# WisolWSSFM10R2-Breakout.net
KiCad netlist of a schematic drawn in EAGLE
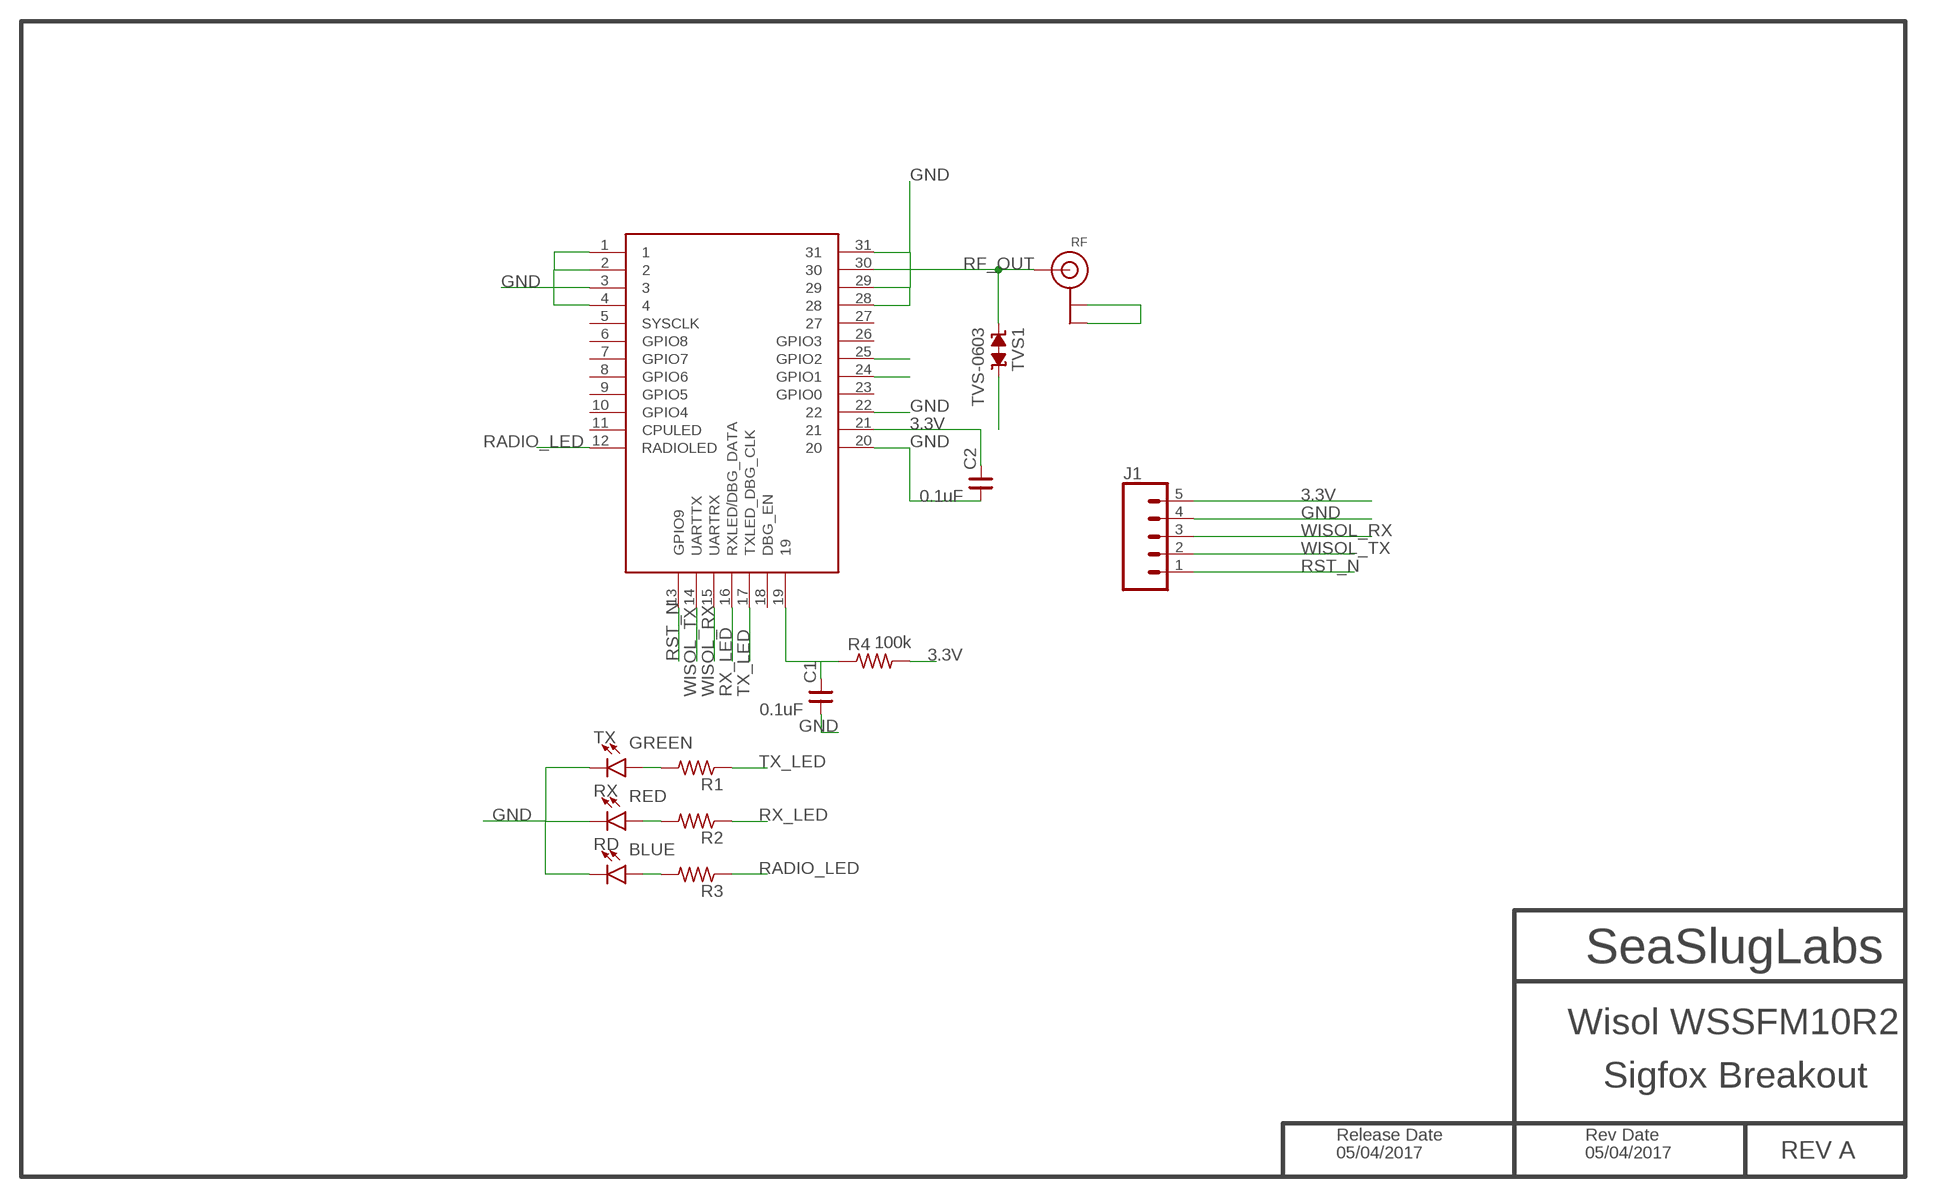
[diagram p0: schematic, sheet 1]

(export (version "E")
  (design (tool "Eeschema 10.0.6"))
  (components
    (comp (ref "C1")
      (value "0.1uF")
      (footprint "eagle-import:0402")
      (libsource (lib "eagle-import") (part "CNP-0402"))
    )
    (comp (ref "C2")
      (value "0.1uF")
      (footprint "eagle-import:0402")
      (libsource (lib "eagle-import") (part "CNP-0402"))
    )
    (comp (ref "J1")
      (value "CONN_05")
      (footprint "eagle-import:1X05")
      (libsource (lib "eagle-import") (part "CONN_05"))
    )
    (comp (ref "R1")
      (value "R-US_R0402")
      (footprint "eagle-import:R0402")
      (libsource (lib "eagle-import") (part "R-US_R0402"))
    )
    (comp (ref "R2")
      (value "R-US_R0402")
      (footprint "eagle-import:R0402")
      (libsource (lib "eagle-import") (part "R-US_R0402"))
    )
    (comp (ref "R3")
      (value "R-US_R0402")
      (footprint "eagle-import:R0402")
      (libsource (lib "eagle-import") (part "R-US_R0402"))
    )
    (comp (ref "R4")
      (value "100k")
      (footprint "eagle-import:R0402")
      (libsource (lib "eagle-import") (part "R-US_R0402"))
    )
    (comp (ref "RD")
      (value "BLUE")
      (footprint "eagle-import:LED-0603")
      (libsource (lib "eagle-import") (part "LED-BLUE0603"))
    )
    (comp (ref "RF")
      (value "ANTENNA_U.FL")
      (footprint "eagle-import:U.FL")
      (libsource (lib "eagle-import") (part "ANTENNA_U.FL"))
    )
    (comp (ref "RX")
      (value "RED")
      (footprint "eagle-import:LED-0603")
      (libsource (lib "eagle-import") (part "LED-RED0603"))
    )
    (comp (ref "TVS1")
      (value "TVS-0603")
      (footprint "eagle-import:TVS0603")
      (libsource (lib "eagle-import") (part "TVS-0603"))
    )
    (comp (ref "TX")
      (value "GREEN")
      (footprint "eagle-import:LED-0603")
      (libsource (lib "eagle-import") (part "LED-GREEN0603"))
    )
    (comp (ref "WSSFM10R2")
      (value "WSSFM10R2/R4WSSFM10R2R4")
      (footprint "eagle-import:WISOL")
      (libsource (lib "eagle-import") (part "WSSFM10R2/R4WSSFM10R2R4"))
    )
  )
  (nets
    (net (code "1") (name "/3.3V") (class "Default")
      (node (ref "C2") (pin "2") (pinfunction "2_2") (pintype "passive"))
      (node (ref "J1") (pin "5") (pinfunction "5_5") (pintype "passive"))
      (node (ref "R4") (pin "2") (pinfunction "2_2") (pintype "passive"))
      (node (ref "WSSFM10R2") (pin "21") (pinfunction "21_21") (pintype "bidirectional"))
    )
    (net (code "2") (name "/GND") (class "Default")
      (node (ref "C1") (pin "1") (pinfunction "1_1") (pintype "passive"))
      (node (ref "C2") (pin "1") (pinfunction "1_1") (pintype "passive"))
      (node (ref "J1") (pin "4") (pinfunction "4_4") (pintype "passive"))
      (node (ref "RD") (pin "C") (pinfunction "C_C") (pintype "passive"))
      (node (ref "RF") (pin "1") (pinfunction "GND_1") (pintype "passive"))
      (node (ref "RF") (pin "2") (pinfunction "GND_2") (pintype "passive"))
      (node (ref "RX") (pin "C") (pinfunction "C_C") (pintype "passive"))
      (node (ref "TVS1") (pin "2") (pinfunction "2_2") (pintype "passive"))
      (node (ref "TX") (pin "C") (pinfunction "C_C") (pintype "passive"))
      (node (ref "WSSFM10R2") (pin "1") (pinfunction "1_1") (pintype "bidirectional"))
      (node (ref "WSSFM10R2") (pin "2") (pinfunction "2_2") (pintype "bidirectional"))
      (node (ref "WSSFM10R2") (pin "20") (pinfunction "20_20") (pintype "bidirectional"))
      (node (ref "WSSFM10R2") (pin "22") (pinfunction "22_22") (pintype "bidirectional"))
      (node (ref "WSSFM10R2") (pin "28") (pinfunction "28_28") (pintype "bidirectional"))
      (node (ref "WSSFM10R2") (pin "29") (pinfunction "29_29") (pintype "bidirectional"))
      (node (ref "WSSFM10R2") (pin "3") (pinfunction "3_3") (pintype "bidirectional"))
      (node (ref "WSSFM10R2") (pin "31") (pinfunction "31_31") (pintype "bidirectional"))
      (node (ref "WSSFM10R2") (pin "4") (pinfunction "4_4") (pintype "bidirectional"))
    )
    (net (code "3") (name "/RADIO_LED") (class "Default")
      (node (ref "R3") (pin "1") (pinfunction "1_1") (pintype "passive"))
      (node (ref "WSSFM10R2") (pin "12") (pinfunction "RADIOLED_12") (pintype "bidirectional"))
    )
    (net (code "4") (name "/RF_OUT") (class "Default")
      (node (ref "RF") (pin "3") (pinfunction "SIGNAL_3") (pintype "passive"))
      (node (ref "TVS1") (pin "1") (pinfunction "1_1") (pintype "passive"))
      (node (ref "WSSFM10R2") (pin "30") (pinfunction "30_30") (pintype "bidirectional"))
    )
    (net (code "5") (name "/RST_N") (class "Default")
      (node (ref "J1") (pin "1") (pinfunction "1_1") (pintype "passive"))
      (node (ref "WSSFM10R2") (pin "13") (pinfunction "GPIO9_13") (pintype "bidirectional"))
    )
    (net (code "6") (name "/RX_LED") (class "Default")
      (node (ref "R2") (pin "1") (pinfunction "1_1") (pintype "passive"))
      (node (ref "WSSFM10R2") (pin "16") (pinfunction "RXLED/DBG_DATA_16") (pintype "bidirectional"))
    )
    (net (code "7") (name "/TX_LED") (class "Default")
      (node (ref "R1") (pin "1") (pinfunction "1_1") (pintype "passive"))
      (node (ref "WSSFM10R2") (pin "17") (pinfunction "TXLED_DBG_CLK_17") (pintype "bidirectional"))
    )
    (net (code "8") (name "/WISOL_RX") (class "Default")
      (node (ref "J1") (pin "3") (pinfunction "3_3") (pintype "passive"))
      (node (ref "WSSFM10R2") (pin "15") (pinfunction "UARTRX_15") (pintype "bidirectional"))
    )
    (net (code "9") (name "/WISOL_TX") (class "Default")
      (node (ref "J1") (pin "2") (pinfunction "2_2") (pintype "passive"))
      (node (ref "WSSFM10R2") (pin "14") (pinfunction "UARTTX_14") (pintype "bidirectional"))
    )
    (net (code "10") (name "Net-(C1-Pad2)") (class "Default")
      (node (ref "C1") (pin "2") (pinfunction "2_2") (pintype "passive"))
      (node (ref "R4") (pin "1") (pinfunction "1_1") (pintype "passive"))
      (node (ref "WSSFM10R2") (pin "19") (pinfunction "19_19") (pintype "bidirectional"))
    )
    (net (code "11") (name "Net-(R1-Pad2)") (class "Default")
      (node (ref "R1") (pin "2") (pinfunction "2_2") (pintype "passive"))
      (node (ref "TX") (pin "A") (pinfunction "A_A") (pintype "passive"))
    )
    (net (code "12") (name "Net-(R2-Pad2)") (class "Default")
      (node (ref "R2") (pin "2") (pinfunction "2_2") (pintype "passive"))
      (node (ref "RX") (pin "A") (pinfunction "A_A") (pintype "passive"))
    )
    (net (code "13") (name "Net-(R3-Pad2)") (class "Default")
      (node (ref "R3") (pin "2") (pinfunction "2_2") (pintype "passive"))
      (node (ref "RD") (pin "A") (pinfunction "A_A") (pintype "passive"))
    )
    (net (code "14") (name "unconnected-(WSSFM10R2-CPULED-Pad11)") (class "Default")
      (node (ref "WSSFM10R2") (pin "11") (pinfunction "CPULED_11") (pintype "bidirectional"))
    )
    (net (code "15") (name "unconnected-(WSSFM10R2-DBG_EN-Pad18)") (class "Default")
      (node (ref "WSSFM10R2") (pin "18") (pinfunction "DBG_EN_18") (pintype "bidirectional"))
    )
    (net (code "16") (name "unconnected-(WSSFM10R2-GPIO0-Pad23)") (class "Default")
      (node (ref "WSSFM10R2") (pin "23") (pinfunction "GPIO0_23") (pintype "bidirectional"))
    )
    (net (code "17") (name "unconnected-(WSSFM10R2-GPIO1-Pad24)") (class "Default")
      (node (ref "WSSFM10R2") (pin "24") (pinfunction "GPIO1_24") (pintype "bidirectional"))
    )
    (net (code "18") (name "unconnected-(WSSFM10R2-GPIO2-Pad25)") (class "Default")
      (node (ref "WSSFM10R2") (pin "25") (pinfunction "GPIO2_25") (pintype "bidirectional"))
    )
    (net (code "19") (name "unconnected-(WSSFM10R2-GPIO3-Pad26)") (class "Default")
      (node (ref "WSSFM10R2") (pin "26") (pinfunction "GPIO3_26") (pintype "bidirectional"))
    )
    (net (code "20") (name "unconnected-(WSSFM10R2-GPIO4-Pad10)") (class "Default")
      (node (ref "WSSFM10R2") (pin "10") (pinfunction "GPIO4_10") (pintype "bidirectional"))
    )
    (net (code "21") (name "unconnected-(WSSFM10R2-GPIO5-Pad9)") (class "Default")
      (node (ref "WSSFM10R2") (pin "9") (pinfunction "GPIO5_9") (pintype "bidirectional"))
    )
    (net (code "22") (name "unconnected-(WSSFM10R2-GPIO6-Pad8)") (class "Default")
      (node (ref "WSSFM10R2") (pin "8") (pinfunction "GPIO6_8") (pintype "bidirectional"))
    )
    (net (code "23") (name "unconnected-(WSSFM10R2-GPIO7-Pad7)") (class "Default")
      (node (ref "WSSFM10R2") (pin "7") (pinfunction "GPIO7_7") (pintype "bidirectional"))
    )
    (net (code "24") (name "unconnected-(WSSFM10R2-GPIO8-Pad6)") (class "Default")
      (node (ref "WSSFM10R2") (pin "6") (pinfunction "GPIO8_6") (pintype "bidirectional"))
    )
    (net (code "25") (name "unconnected-(WSSFM10R2-Pad27)") (class "Default")
      (node (ref "WSSFM10R2") (pin "27") (pinfunction "27_27") (pintype "bidirectional"))
    )
    (net (code "26") (name "unconnected-(WSSFM10R2-SYSCLK-Pad5)") (class "Default")
      (node (ref "WSSFM10R2") (pin "5") (pinfunction "SYSCLK_5") (pintype "bidirectional"))
    )
  )
)
